# femtoUSB_r1_0_1_BREADBOARD.net
KiCad netlist of a schematic drawn in EAGLE
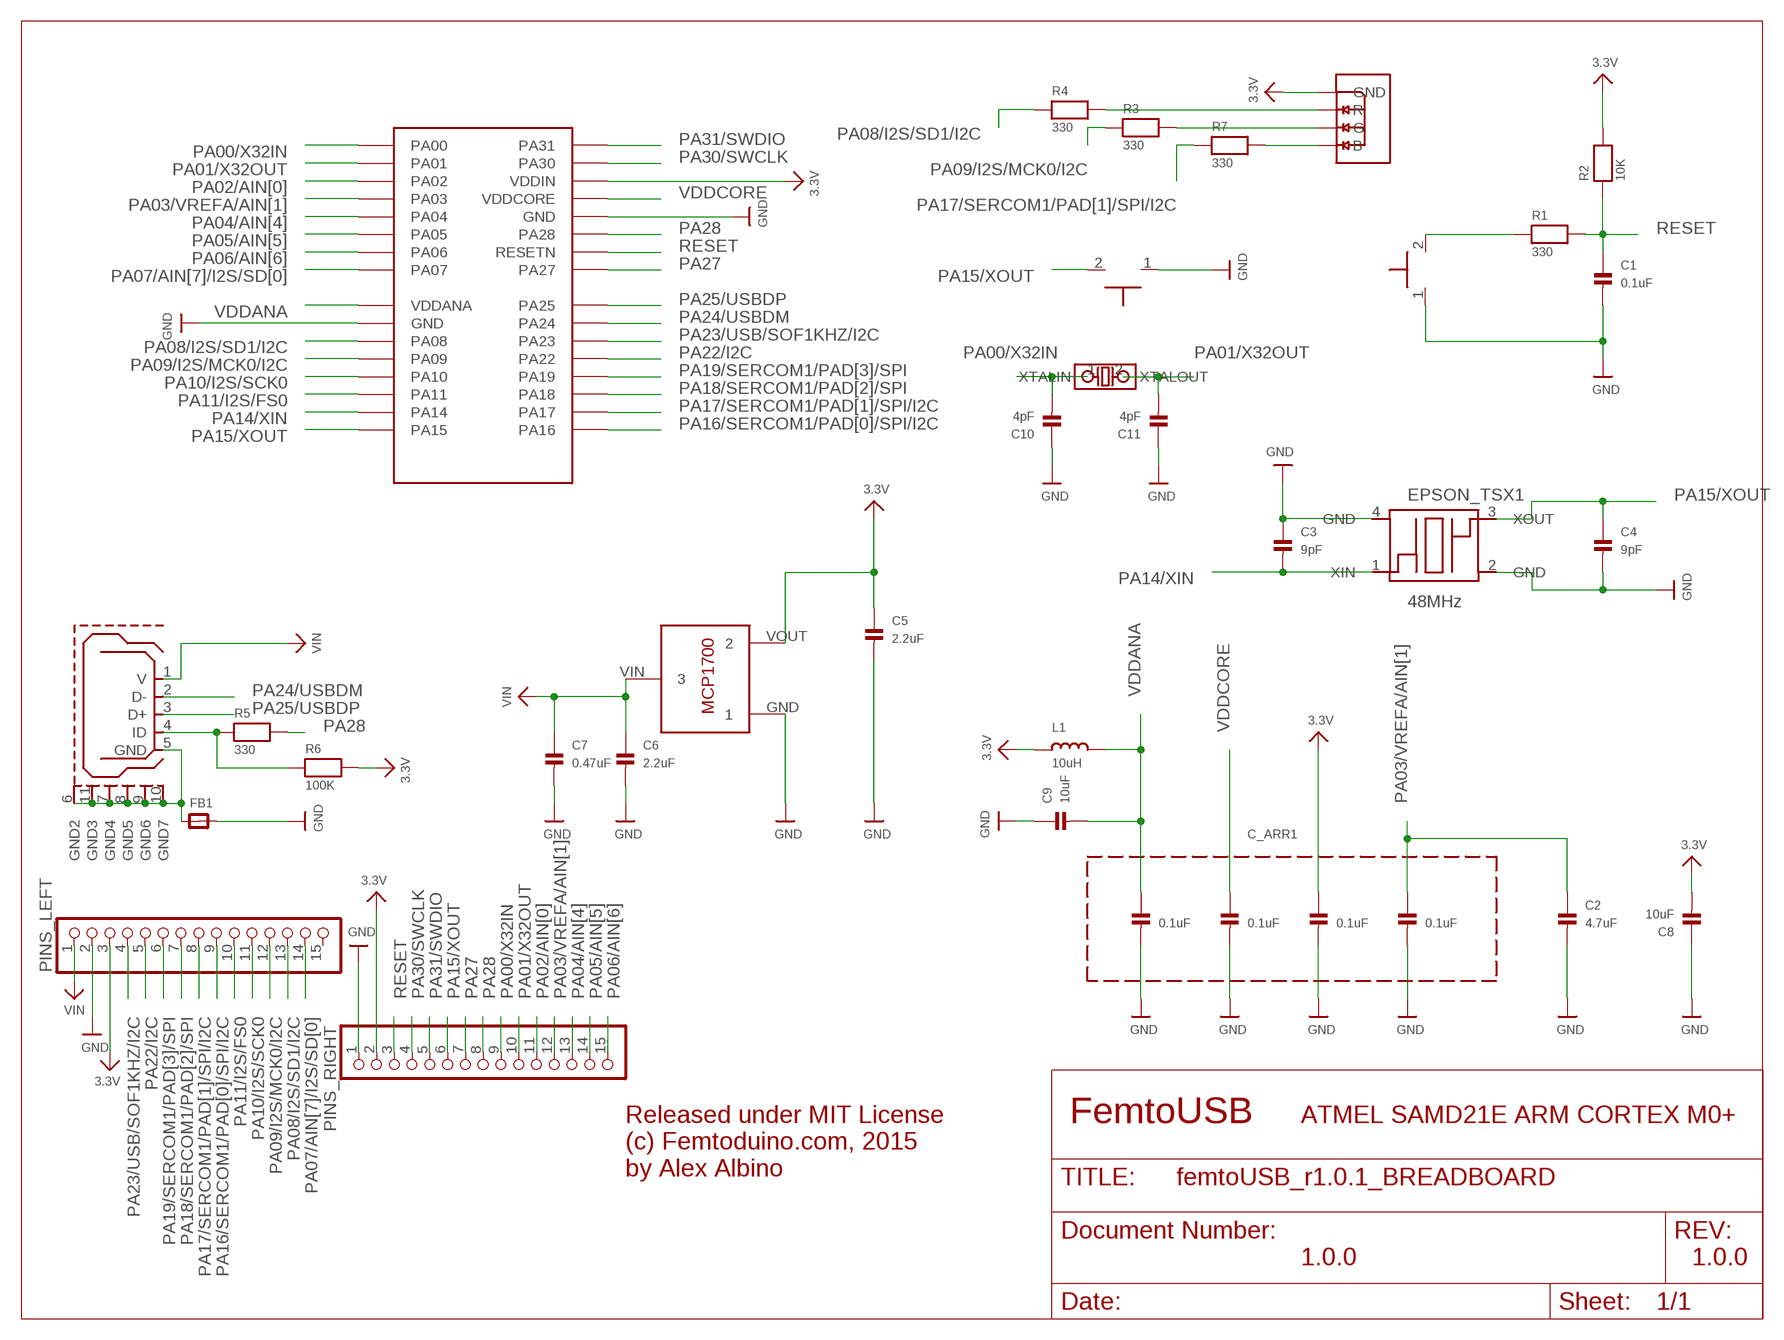
[diagram p0: schematic, sheet 1]

(export (version "E")
  (design (tool "Eeschema 10.0.6"))
  (components
    (comp (ref "BOOT_BTN")
      (value "TACTILE_SWITCH_NO_GND_NO_BOSS")
      (footprint "eagle-import:SIDE_ACT_NO_GND_NO_BOSS")
      (libsource (lib "eagle-import") (part "TACTILE_SWITCH_NO_GND_NO_BOSS"))
    )
    (comp (ref "BOOT_BTN1")
      (value "TACTILE_SWITCH_NO_GND_NO_BOSS")
      (footprint "eagle-import:SIDE_ACT_NO_GND_NO_BOSS")
      (libsource (lib "eagle-import") (part "TACTILE_SWITCH_NO_GND_NO_BOSS"))
    )
    (comp (ref "C1")
      (value "0.1uF")
      (footprint "eagle-import:_0402MP")
      (fields (field (name "DIGIKEY_PART") "445-4958-1-ND"))
      (libsource (lib "eagle-import") (part "CAP_CERAMIC_0402MP"))
    )
    (comp (ref "C2")
      (value "4.7uF")
      (footprint "eagle-import:_0402MP")
      (libsource (lib "eagle-import") (part "CAP_CERAMIC_0402MP"))
    )
    (comp (ref "C3")
      (value "9pF")
      (footprint "eagle-import:_0402MP")
      (libsource (lib "eagle-import") (part "CAP_CERAMIC_0402MP"))
    )
    (comp (ref "C4")
      (value "9pF")
      (footprint "eagle-import:_0402MP")
      (libsource (lib "eagle-import") (part "CAP_CERAMIC_0402MP"))
    )
    (comp (ref "C5")
      (value "2.2uF")
      (footprint "eagle-import:_0402MP")
      (libsource (lib "eagle-import") (part "CAP_CERAMIC_0402MP"))
    )
    (comp (ref "C6")
      (value "2.2uF")
      (footprint "eagle-import:_0402MP")
      (libsource (lib "eagle-import") (part "CAP_CERAMIC_0402MP"))
    )
    (comp (ref "C7")
      (value "0.47uF")
      (footprint "eagle-import:_0402MP")
      (libsource (lib "eagle-import") (part "CAP_CERAMIC_0402MP"))
    )
    (comp (ref "C8")
      (value "10uF")
      (footprint "eagle-import:_0402MP")
      (libsource (lib "eagle-import") (part "CAP_CERAMIC_0402MP"))
    )
    (comp (ref "C9")
      (value "10uF")
      (footprint "eagle-import:_0402MP")
      (libsource (lib "eagle-import") (part "CAP_CERAMIC_0402MP"))
    )
    (comp (ref "C10")
      (value "4pF")
      (footprint "eagle-import:_0402MP")
      (libsource (lib "eagle-import") (part "CAP_CERAMIC_0402MP"))
    )
    (comp (ref "C11")
      (value "4pF")
      (footprint "eagle-import:_0402MP")
      (libsource (lib "eagle-import") (part "CAP_CERAMIC_0402MP"))
    )
    (comp (ref "C_ARR1")
      (value "0.1uF")
      (footprint "eagle-import:CAPACITOR_ARRAY_1206_MONO_1X4")
      (libsource (lib "eagle-import") (part "KEMET_CERAMIC_CAPACITOR_ARRAY_1X4"))
    )
    (comp (ref "EPSON_TSX1")
      (value "48MHz")
      (footprint "eagle-import:TSX-3225")
      (fields (field (name "DIGIKEY_PART") "TSX-3225 32.0000MF15X-B-ND"))
      (libsource (lib "eagle-import") (part "TSX-3225"))
    )
    (comp (ref "FB1")
      (value "FERRITE_0603MP")
      (footprint "eagle-import:_0603MP")
      (libsource (lib "eagle-import") (part "FERRITE_0603MP"))
    )
    (comp (ref "IC1")
      (value "ATSAMD21E18A-MUT")
      (footprint "eagle-import:QFN32")
      (fields (field (name "DIGIKEY_PART") "ATSAMD21E18A-AU-ND"))
      (libsource (lib "eagle-import") (part "ATSAMD21E18A-MUT"))
    )
    (comp (ref "L1")
      (value "10uH")
      (footprint "eagle-import:_0603MP")
      (libsource (lib "eagle-import") (part "INDUCTOR_0603MP"))
    )
    (comp (ref "LDO_VREG")
      (value "MCP1700T-3302E/TT")
      (footprint "eagle-import:MCP1700T-3302E_TT")
      (libsource (lib "eagle-import") (part "MCP1700T-3302E/TT"))
    )
    (comp (ref "MICRO_B_USB")
      (value "USB_MICROB")
      (footprint "eagle-import:USB_MICROB_PACKAGE")
      (libsource (lib "eagle-import") (part "USB_MICROB"))
    )
    (comp (ref "PINS_LEFT")
      (value "HEADER-1X15")
      (footprint "eagle-import:1X15_ROUND_70")
      (libsource (lib "eagle-import") (part "HEADER-1X15"))
    )
    (comp (ref "PINS_RIGHT")
      (value "HEADER-1X15")
      (footprint "eagle-import:1X15_ROUND_70")
      (libsource (lib "eagle-import") (part "HEADER-1X15"))
    )
    (comp (ref "R1")
      (value "330")
      (footprint "eagle-import:_0402MP")
      (fields (field (name "DIGIKEY_PART") "541-330JCT-ND"))
      (libsource (lib "eagle-import") (part "RESISTOR_0402MP"))
    )
    (comp (ref "R2")
      (value "10K")
      (footprint "eagle-import:_0402MP")
      (libsource (lib "eagle-import") (part "RESISTOR_0402MP"))
    )
    (comp (ref "R3")
      (value "330")
      (footprint "eagle-import:_0402MP")
      (libsource (lib "eagle-import") (part "RESISTOR_0402MP"))
    )
    (comp (ref "R4")
      (value "330")
      (footprint "eagle-import:_0402MP")
      (libsource (lib "eagle-import") (part "RESISTOR_0402MP"))
    )
    (comp (ref "R5")
      (value "330")
      (footprint "eagle-import:_0402MP")
      (libsource (lib "eagle-import") (part "RESISTOR_0402MP"))
    )
    (comp (ref "R6")
      (value "100K")
      (footprint "eagle-import:_0402MP")
      (libsource (lib "eagle-import") (part "RESISTOR_0402MP"))
    )
    (comp (ref "R7")
      (value "330")
      (footprint "eagle-import:_0402MP")
      (libsource (lib "eagle-import") (part "RESISTOR_0402MP"))
    )
    (comp (ref "RGBLED")
      (value "LRTB_R48G")
      (footprint "eagle-import:LRTB_R48G")
      (libsource (lib "eagle-import") (part "LRTB_R48G"))
    )
    (comp (ref "U$40")
      (value "ABS06-107-32.768KHZ-T")
      (footprint "eagle-import:ABS06-107-32.768KHZ-T")
      (libsource (lib "eagle-import") (part "ABS06-107-32.768KHZ-T"))
    )
  )
  (nets
    (net (code "1") (name "/PA00{slash}X32IN") (class "Default")
      (node (ref "C10") (pin "2") (pinfunction "P$2_2") (pintype "passive"))
      (node (ref "IC1") (pin "1") (pinfunction "PA00_1") (pintype "bidirectional"))
      (node (ref "PINS_RIGHT") (pin "9") (pinfunction "9_9") (pintype "passive"))
      (node (ref "U$40") (pin "1") (pinfunction "XTALIN_1") (pintype "bidirectional"))
    )
    (net (code "2") (name "/PA01{slash}X32OUT") (class "Default")
      (node (ref "C11") (pin "2") (pinfunction "P$2_2") (pintype "passive"))
      (node (ref "IC1") (pin "2") (pinfunction "PA01_2") (pintype "bidirectional"))
      (node (ref "PINS_RIGHT") (pin "10") (pinfunction "10_10") (pintype "passive"))
      (node (ref "U$40") (pin "2") (pinfunction "XTALOUT_2") (pintype "bidirectional"))
    )
    (net (code "3") (name "/PA02{slash}AIN[0]") (class "Default")
      (node (ref "IC1") (pin "3") (pinfunction "PA02_3") (pintype "bidirectional"))
      (node (ref "PINS_RIGHT") (pin "11") (pinfunction "11_11") (pintype "passive"))
    )
    (net (code "4") (name "/PA03{slash}VREFA{slash}AIN[1]") (class "Default")
      (node (ref "C2") (pin "1") (pinfunction "P$1_1") (pintype "passive"))
      (node (ref "C_ARR1") (pin "7") (pinfunction "P$7_7") (pintype "passive"))
      (node (ref "IC1") (pin "4") (pinfunction "PA03_4") (pintype "bidirectional"))
      (node (ref "PINS_RIGHT") (pin "12") (pinfunction "12_12") (pintype "passive"))
    )
    (net (code "5") (name "/PA04{slash}AIN[4]") (class "Default")
      (node (ref "IC1") (pin "5") (pinfunction "PA04_5") (pintype "bidirectional"))
      (node (ref "PINS_RIGHT") (pin "13") (pinfunction "13_13") (pintype "passive"))
    )
    (net (code "6") (name "/PA05{slash}AIN[5]") (class "Default")
      (node (ref "IC1") (pin "6") (pinfunction "PA05_6") (pintype "bidirectional"))
      (node (ref "PINS_RIGHT") (pin "14") (pinfunction "14_14") (pintype "passive"))
    )
    (net (code "7") (name "/PA06{slash}AIN[6]") (class "Default")
      (node (ref "IC1") (pin "7") (pinfunction "PA06_7") (pintype "bidirectional"))
      (node (ref "PINS_RIGHT") (pin "15") (pinfunction "15_15") (pintype "passive"))
    )
    (net (code "8") (name "/PA07{slash}AIN[7]{slash}I2S{slash}SD[0]") (class "Default")
      (node (ref "IC1") (pin "8") (pinfunction "PA07_8") (pintype "bidirectional"))
      (node (ref "PINS_LEFT") (pin "14") (pinfunction "14_14") (pintype "passive"))
    )
    (net (code "9") (name "/PA08{slash}I2S{slash}SD1{slash}I2C") (class "Default")
      (node (ref "IC1") (pin "11") (pinfunction "PA08_11") (pintype "bidirectional"))
      (node (ref "PINS_LEFT") (pin "13") (pinfunction "13_13") (pintype "passive"))
      (node (ref "R4") (pin "1") (pinfunction "1_1") (pintype "passive"))
    )
    (net (code "10") (name "/PA09{slash}I2S{slash}MCK0{slash}I2C") (class "Default")
      (node (ref "IC1") (pin "12") (pinfunction "PA09_12") (pintype "bidirectional"))
      (node (ref "PINS_LEFT") (pin "12") (pinfunction "12_12") (pintype "passive"))
      (node (ref "R3") (pin "1") (pinfunction "1_1") (pintype "passive"))
    )
    (net (code "11") (name "/PA10{slash}I2S{slash}SCK0") (class "Default")
      (node (ref "IC1") (pin "13") (pinfunction "PA10_13") (pintype "bidirectional"))
      (node (ref "PINS_LEFT") (pin "11") (pinfunction "11_11") (pintype "passive"))
    )
    (net (code "12") (name "/PA11{slash}I2S{slash}FS0") (class "Default")
      (node (ref "IC1") (pin "14") (pinfunction "PA11_14") (pintype "bidirectional"))
      (node (ref "PINS_LEFT") (pin "10") (pinfunction "10_10") (pintype "passive"))
    )
    (net (code "13") (name "/PA14{slash}XIN") (class "Default")
      (node (ref "C3") (pin "2") (pinfunction "P$2_2") (pintype "passive"))
      (node (ref "EPSON_TSX1") (pin "1") (pinfunction "XIN_1") (pintype "bidirectional"))
      (node (ref "IC1") (pin "15") (pinfunction "PA14_15") (pintype "bidirectional"))
    )
    (net (code "14") (name "/PA15{slash}XOUT") (class "Default")
      (node (ref "BOOT_BTN") (pin "2") (pinfunction "2_2") (pintype "bidirectional"))
      (node (ref "C4") (pin "1") (pinfunction "P$1_1") (pintype "passive"))
      (node (ref "EPSON_TSX1") (pin "3") (pinfunction "XOUT_3") (pintype "bidirectional"))
      (node (ref "IC1") (pin "16") (pinfunction "PA15_16") (pintype "bidirectional"))
      (node (ref "PINS_RIGHT") (pin "6") (pinfunction "6_6") (pintype "passive"))
    )
    (net (code "15") (name "/PA16{slash}SERCOM1{slash}PAD[0]{slash}SPI{slash}I2C") (class "Default")
      (node (ref "IC1") (pin "17") (pinfunction "PA16_17") (pintype "bidirectional"))
      (node (ref "PINS_LEFT") (pin "9") (pinfunction "9_9") (pintype "passive"))
    )
    (net (code "16") (name "/PA17{slash}SERCOM1{slash}PAD[1]{slash}SPI{slash}I2C") (class "Default")
      (node (ref "IC1") (pin "18") (pinfunction "PA17_18") (pintype "bidirectional"))
      (node (ref "PINS_LEFT") (pin "8") (pinfunction "8_8") (pintype "passive"))
      (node (ref "R7") (pin "1") (pinfunction "1_1") (pintype "passive"))
    )
    (net (code "17") (name "/PA18{slash}SERCOM1{slash}PAD[2]{slash}SPI") (class "Default")
      (node (ref "IC1") (pin "19") (pinfunction "PA18_19") (pintype "bidirectional"))
      (node (ref "PINS_LEFT") (pin "7") (pinfunction "7_7") (pintype "passive"))
    )
    (net (code "18") (name "/PA19{slash}SERCOM1{slash}PAD[3]{slash}SPI") (class "Default")
      (node (ref "IC1") (pin "20") (pinfunction "PA19_20") (pintype "bidirectional"))
      (node (ref "PINS_LEFT") (pin "6") (pinfunction "6_6") (pintype "passive"))
    )
    (net (code "19") (name "/PA22{slash}I2C") (class "Default")
      (node (ref "IC1") (pin "21") (pinfunction "PA22_21") (pintype "bidirectional"))
      (node (ref "PINS_LEFT") (pin "5") (pinfunction "5_5") (pintype "passive"))
    )
    (net (code "20") (name "/PA23{slash}USB{slash}SOF1KHZ{slash}I2C") (class "Default")
      (node (ref "IC1") (pin "22") (pinfunction "PA23_22") (pintype "bidirectional"))
      (node (ref "PINS_LEFT") (pin "4") (pinfunction "4_4") (pintype "passive"))
    )
    (net (code "21") (name "/PA24{slash}USBDM") (class "Default")
      (node (ref "IC1") (pin "23") (pinfunction "PA24_23") (pintype "bidirectional"))
      (node (ref "MICRO_B_USB") (pin "2") (pinfunction "D-_2") (pintype "bidirectional"))
    )
    (net (code "22") (name "/PA25{slash}USBDP") (class "Default")
      (node (ref "IC1") (pin "24") (pinfunction "PA25_24") (pintype "bidirectional"))
      (node (ref "MICRO_B_USB") (pin "3") (pinfunction "D+_3") (pintype "bidirectional"))
    )
    (net (code "23") (name "/PA27") (class "Default")
      (node (ref "IC1") (pin "25") (pinfunction "PA27_25") (pintype "bidirectional"))
      (node (ref "PINS_RIGHT") (pin "7") (pinfunction "7_7") (pintype "passive"))
    )
    (net (code "24") (name "/PA28") (class "Default")
      (node (ref "IC1") (pin "27") (pinfunction "PA28_27") (pintype "bidirectional"))
      (node (ref "PINS_RIGHT") (pin "8") (pinfunction "8_8") (pintype "passive"))
      (node (ref "R5") (pin "2") (pinfunction "2_2") (pintype "passive"))
    )
    (net (code "25") (name "/PA30{slash}SWCLK") (class "Default")
      (node (ref "IC1") (pin "31") (pinfunction "PA30_31") (pintype "bidirectional"))
      (node (ref "PINS_RIGHT") (pin "4") (pinfunction "4_4") (pintype "passive"))
    )
    (net (code "26") (name "/PA31{slash}SWDIO") (class "Default")
      (node (ref "IC1") (pin "32") (pinfunction "PA31_32") (pintype "bidirectional"))
      (node (ref "PINS_RIGHT") (pin "5") (pinfunction "5_5") (pintype "passive"))
    )
    (net (code "27") (name "/RESET") (class "Default")
      (node (ref "C1") (pin "1") (pinfunction "P$1_1") (pintype "passive"))
      (node (ref "IC1") (pin "26") (pinfunction "RESETN_26") (pintype "bidirectional"))
      (node (ref "PINS_RIGHT") (pin "3") (pinfunction "3_3") (pintype "passive"))
      (node (ref "R1") (pin "2") (pinfunction "2_2") (pintype "passive"))
      (node (ref "R2") (pin "1") (pinfunction "1_1") (pintype "passive"))
    )
    (net (code "28") (name "/VDDANA") (class "Default")
      (node (ref "C9") (pin "2") (pinfunction "P$2_2") (pintype "passive"))
      (node (ref "C_ARR1") (pin "1") (pinfunction "P$1_1") (pintype "passive"))
      (node (ref "IC1") (pin "9") (pinfunction "VDDANA_9") (pintype "bidirectional"))
      (node (ref "L1") (pin "2") (pinfunction "2_2") (pintype "passive"))
    )
    (net (code "29") (name "/VDDCORE") (class "Default")
      (node (ref "C_ARR1") (pin "3") (pinfunction "P$3_3") (pintype "passive"))
      (node (ref "IC1") (pin "29") (pinfunction "VDDCORE_29") (pintype "bidirectional"))
    )
    (net (code "30") (name "3.3V") (class "Default")
      (node (ref "C5") (pin "1") (pinfunction "P$1_1") (pintype "passive"))
      (node (ref "C8") (pin "2") (pinfunction "P$2_2") (pintype "passive"))
      (node (ref "C_ARR1") (pin "5") (pinfunction "P$5_5") (pintype "passive"))
      (node (ref "IC1") (pin "30") (pinfunction "VDDIN_30") (pintype "bidirectional"))
      (node (ref "L1") (pin "1") (pinfunction "1_1") (pintype "passive"))
      (node (ref "LDO_VREG") (pin "VOUT") (pinfunction "2_VOUT") (pintype "bidirectional"))
      (node (ref "PINS_LEFT") (pin "3") (pinfunction "3_3") (pintype "passive"))
      (node (ref "PINS_RIGHT") (pin "2") (pinfunction "2_2") (pintype "passive"))
      (node (ref "R2") (pin "2") (pinfunction "2_2") (pintype "passive"))
      (node (ref "R6") (pin "2") (pinfunction "2_2") (pintype "passive"))
      (node (ref "RGBLED") (pin "1") (pinfunction "GND_1") (pintype "bidirectional"))
    )
    (net (code "31") (name "GND") (class "Default")
      (node (ref "BOOT_BTN") (pin "1") (pinfunction "1_1") (pintype "bidirectional"))
      (node (ref "BOOT_BTN1") (pin "1") (pinfunction "1_1") (pintype "bidirectional"))
      (node (ref "C1") (pin "2") (pinfunction "P$2_2") (pintype "passive"))
      (node (ref "C10") (pin "1") (pinfunction "P$1_1") (pintype "passive"))
      (node (ref "C11") (pin "1") (pinfunction "P$1_1") (pintype "passive"))
      (node (ref "C2") (pin "2") (pinfunction "P$2_2") (pintype "passive"))
      (node (ref "C3") (pin "1") (pinfunction "P$1_1") (pintype "passive"))
      (node (ref "C4") (pin "2") (pinfunction "P$2_2") (pintype "passive"))
      (node (ref "C5") (pin "2") (pinfunction "P$2_2") (pintype "passive"))
      (node (ref "C6") (pin "2") (pinfunction "P$2_2") (pintype "passive"))
      (node (ref "C7") (pin "2") (pinfunction "P$2_2") (pintype "passive"))
      (node (ref "C8") (pin "1") (pinfunction "P$1_1") (pintype "passive"))
      (node (ref "C9") (pin "1") (pinfunction "P$1_1") (pintype "passive"))
      (node (ref "C_ARR1") (pin "2") (pinfunction "P$2_2") (pintype "passive"))
      (node (ref "C_ARR1") (pin "4") (pinfunction "P$4_4") (pintype "passive"))
      (node (ref "C_ARR1") (pin "6") (pinfunction "P$6_6") (pintype "passive"))
      (node (ref "C_ARR1") (pin "8") (pinfunction "P$8_8") (pintype "passive"))
      (node (ref "EPSON_TSX1") (pin "2") (pinfunction "GND_2") (pintype "bidirectional"))
      (node (ref "EPSON_TSX1") (pin "4") (pinfunction "GND_4") (pintype "bidirectional"))
      (node (ref "FB1") (pin "2") (pinfunction "P$2_2") (pintype "passive"))
      (node (ref "IC1") (pin "10") (pinfunction "GND_10") (pintype "bidirectional"))
      (node (ref "IC1") (pin "28") (pinfunction "GND_28") (pintype "bidirectional"))
      (node (ref "LDO_VREG") (pin "GND") (pinfunction "1_GND") (pintype "bidirectional"))
      (node (ref "PINS_LEFT") (pin "2") (pinfunction "2_2") (pintype "passive"))
      (node (ref "PINS_RIGHT") (pin "1") (pinfunction "1_1") (pintype "passive"))
    )
    (net (code "32") (name "Net-(BOOT_BTN1-Pad2)") (class "Default")
      (node (ref "BOOT_BTN1") (pin "2") (pinfunction "2_2") (pintype "bidirectional"))
      (node (ref "R1") (pin "1") (pinfunction "1_1") (pintype "passive"))
    )
    (net (code "33") (name "Net-(FB1-P$1)") (class "Default")
      (node (ref "FB1") (pin "1") (pinfunction "P$1_1") (pintype "passive"))
      (node (ref "MICRO_B_USB") (pin "10") (pinfunction "GND7_10") (pintype "bidirectional"))
      (node (ref "MICRO_B_USB") (pin "11") (pinfunction "GND3_11") (pintype "bidirectional"))
      (node (ref "MICRO_B_USB") (pin "5") (pinfunction "GND_5") (pintype "bidirectional"))
      (node (ref "MICRO_B_USB") (pin "6") (pinfunction "GND2_6") (pintype "bidirectional"))
      (node (ref "MICRO_B_USB") (pin "7") (pinfunction "GND4_7") (pintype "bidirectional"))
      (node (ref "MICRO_B_USB") (pin "8") (pinfunction "GND5_8") (pintype "bidirectional"))
      (node (ref "MICRO_B_USB") (pin "9") (pinfunction "GND6_9") (pintype "bidirectional"))
    )
    (net (code "34") (name "Net-(MICRO_B_USB-ID)") (class "Default")
      (node (ref "MICRO_B_USB") (pin "4") (pinfunction "ID_4") (pintype "bidirectional"))
      (node (ref "R5") (pin "1") (pinfunction "1_1") (pintype "passive"))
      (node (ref "R6") (pin "1") (pinfunction "1_1") (pintype "passive"))
    )
    (net (code "35") (name "Net-(RGBLED-B)") (class "Default")
      (node (ref "R7") (pin "2") (pinfunction "2_2") (pintype "passive"))
      (node (ref "RGBLED") (pin "4") (pinfunction "B_4") (pintype "bidirectional"))
    )
    (net (code "36") (name "Net-(RGBLED-G)") (class "Default")
      (node (ref "R3") (pin "2") (pinfunction "2_2") (pintype "passive"))
      (node (ref "RGBLED") (pin "3") (pinfunction "G_3") (pintype "bidirectional"))
    )
    (net (code "37") (name "Net-(RGBLED-R)") (class "Default")
      (node (ref "R4") (pin "2") (pinfunction "2_2") (pintype "passive"))
      (node (ref "RGBLED") (pin "2") (pinfunction "R_2") (pintype "bidirectional"))
    )
    (net (code "38") (name "VIN") (class "Default")
      (node (ref "C6") (pin "1") (pinfunction "P$1_1") (pintype "passive"))
      (node (ref "C7") (pin "1") (pinfunction "P$1_1") (pintype "passive"))
      (node (ref "LDO_VREG") (pin "VIN") (pinfunction "3_VIN") (pintype "bidirectional"))
      (node (ref "MICRO_B_USB") (pin "1") (pinfunction "V_1") (pintype "bidirectional"))
      (node (ref "PINS_LEFT") (pin "1") (pinfunction "1_1") (pintype "passive"))
    )
    (net (code "39") (name "unconnected-(PINS_LEFT-Pad15)") (class "Default")
      (node (ref "PINS_LEFT") (pin "15") (pinfunction "15_15") (pintype "passive"))
    )
  )
)
